# RPiHeatingArduinoOilSensor433.net
KiCad netlist of a schematic drawn in EAGLE
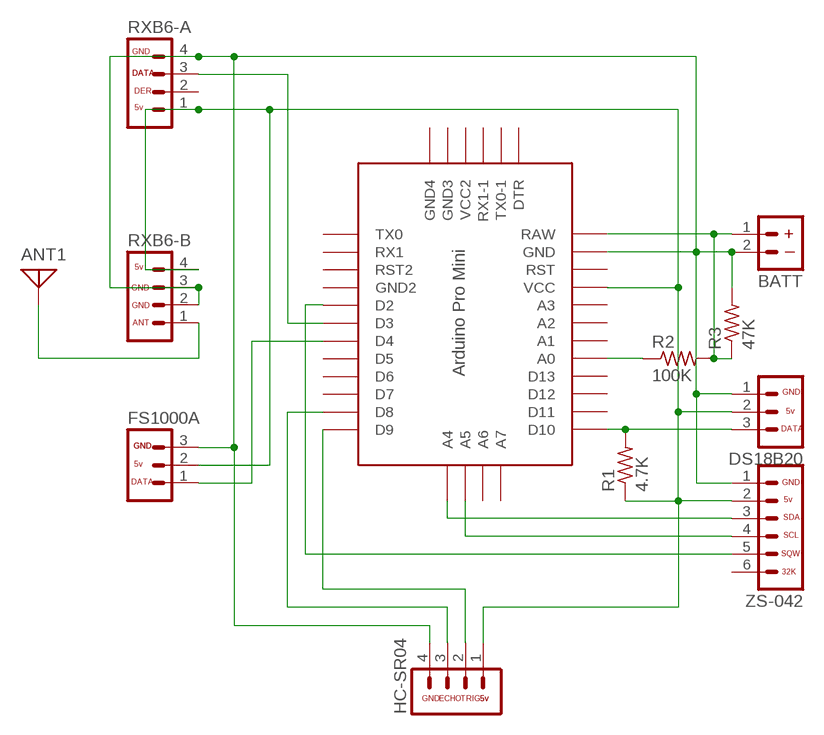
[diagram p0: schematic, sheet 1]

(export (version "E")
  (design (tool "Eeschema 10.0.6"))
  (components
    (comp (ref "ANT1")
      (value "ANTENNA")
      (footprint "eagle-import:PAD-01")
      (libsource (lib "eagle-import") (part "ANTENNA"))
    )
    (comp (ref "BATT")
      (value "M02PTH")
      (footprint "eagle-import:1X02")
      (libsource (lib "eagle-import") (part "M02PTH"))
    )
    (comp (ref "DS18B20")
      (value "M03JST-PTH-VERT")
      (footprint "eagle-import:JST-3-PTH-VERT")
      (libsource (lib "eagle-import") (part "M03JST-PTH-VERT"))
    )
    (comp (ref "FS1000A")
      (value "M03LONGPADS")
      (footprint "eagle-import:1X03_LONGPADS")
      (libsource (lib "eagle-import") (part "M03LONGPADS"))
    )
    (comp (ref "HC-SR04")
      (value "M04LONGPADS")
      (footprint "eagle-import:1X04_LONGPADS")
      (libsource (lib "eagle-import") (part "M04LONGPADS"))
    )
    (comp (ref "R1")
      (value "4.7K")
      (footprint "eagle-import:0204_7")
      (libsource (lib "eagle-import") (part "R-US_0204/7"))
    )
    (comp (ref "R2")
      (value "100K")
      (footprint "eagle-import:0207_10")
      (libsource (lib "eagle-import") (part "R-US_0207/10"))
    )
    (comp (ref "R3")
      (value "47K")
      (footprint "eagle-import:0207_10")
      (libsource (lib "eagle-import") (part "R-US_0207/10"))
    )
    (comp (ref "RXB6-A")
      (value "M04LONGPADS")
      (footprint "eagle-import:1X04_LONGPADS")
      (libsource (lib "eagle-import") (part "M04LONGPADS"))
    )
    (comp (ref "RXB6-B")
      (value "M04LONGPADS")
      (footprint "eagle-import:1X04_LONGPADS")
      (libsource (lib "eagle-import") (part "M04LONGPADS"))
    )
    (comp (ref "U$1")
      (value "PRO-MINI")
      (footprint "eagle-import:PRO-MINI")
      (libsource (lib "eagle-import") (part "PRO-MINI"))
    )
    (comp (ref "ZS-042")
      (value "M06LONGPADS")
      (footprint "eagle-import:1X06_LONGPADS")
      (libsource (lib "eagle-import") (part "M06LONGPADS"))
    )
  )
  (nets
    (net (code "1") (name "Net-(ANT1-Pad1)") (class "Default")
      (node (ref "ANT1") (pin "1") (pinfunction "1_1") (pintype "output"))
      (node (ref "RXB6-B") (pin "1") (pinfunction "1_1") (pintype "passive"))
    )
    (net (code "2") (name "Net-(BATT-Pad1)") (class "Default")
      (node (ref "BATT") (pin "1") (pinfunction "1_1") (pintype "passive"))
      (node (ref "R2") (pin "2") (pinfunction "2_2") (pintype "passive"))
      (node (ref "R3") (pin "1") (pinfunction "1_1") (pintype "passive"))
      (node (ref "U$1") (pin "RAW") (pinfunction "RAW_RAW") (pintype "power_in"))
    )
    (net (code "3") (name "Net-(BATT-Pad2)") (class "Default")
      (node (ref "BATT") (pin "2") (pinfunction "2_2") (pintype "passive"))
      (node (ref "DS18B20") (pin "1") (pinfunction "1_1") (pintype "passive"))
      (node (ref "FS1000A") (pin "3") (pinfunction "3_3") (pintype "passive"))
      (node (ref "HC-SR04") (pin "4") (pinfunction "4_4") (pintype "passive"))
      (node (ref "R3") (pin "2") (pinfunction "2_2") (pintype "passive"))
      (node (ref "RXB6-A") (pin "4") (pinfunction "4_4") (pintype "passive"))
      (node (ref "RXB6-B") (pin "2") (pinfunction "2_2") (pintype "passive"))
      (node (ref "RXB6-B") (pin "3") (pinfunction "3_3") (pintype "passive"))
      (node (ref "U$1") (pin "GND") (pinfunction "GND_GND") (pintype "input"))
      (node (ref "ZS-042") (pin "1") (pinfunction "1_1") (pintype "passive"))
    )
    (net (code "4") (name "Net-(DS18B20-Pad2)") (class "Default")
      (node (ref "DS18B20") (pin "2") (pinfunction "2_2") (pintype "passive"))
      (node (ref "FS1000A") (pin "2") (pinfunction "2_2") (pintype "passive"))
      (node (ref "HC-SR04") (pin "1") (pinfunction "1_1") (pintype "passive"))
      (node (ref "R1") (pin "1") (pinfunction "1_1") (pintype "passive"))
      (node (ref "RXB6-A") (pin "1") (pinfunction "1_1") (pintype "passive"))
      (node (ref "RXB6-B") (pin "4") (pinfunction "4_4") (pintype "passive"))
      (node (ref "U$1") (pin "VCC") (pinfunction "VCC_VCC") (pintype "bidirectional"))
      (node (ref "ZS-042") (pin "2") (pinfunction "2_2") (pintype "passive"))
    )
    (net (code "5") (name "Net-(DS18B20-Pad3)") (class "Default")
      (node (ref "DS18B20") (pin "3") (pinfunction "3_3") (pintype "passive"))
      (node (ref "R1") (pin "2") (pinfunction "2_2") (pintype "passive"))
      (node (ref "U$1") (pin "D10") (pinfunction "D10_D10") (pintype "bidirectional"))
    )
    (net (code "6") (name "Net-(FS1000A-Pad1)") (class "Default")
      (node (ref "FS1000A") (pin "1") (pinfunction "1_1") (pintype "passive"))
      (node (ref "U$1") (pin "D4") (pinfunction "D4_D4") (pintype "bidirectional"))
    )
    (net (code "7") (name "Net-(HC-SR04-Pad2)") (class "Default")
      (node (ref "HC-SR04") (pin "2") (pinfunction "2_2") (pintype "passive"))
      (node (ref "U$1") (pin "D9") (pinfunction "D9_D9") (pintype "bidirectional"))
    )
    (net (code "8") (name "Net-(HC-SR04-Pad3)") (class "Default")
      (node (ref "HC-SR04") (pin "3") (pinfunction "3_3") (pintype "passive"))
      (node (ref "U$1") (pin "D8") (pinfunction "D8_D8") (pintype "bidirectional"))
    )
    (net (code "9") (name "Net-(R2-Pad1)") (class "Default")
      (node (ref "R2") (pin "1") (pinfunction "1_1") (pintype "passive"))
      (node (ref "U$1") (pin "A0") (pinfunction "A0_A0") (pintype "bidirectional"))
    )
    (net (code "10") (name "Net-(RXB6-A-Pad3)") (class "Default")
      (node (ref "RXB6-A") (pin "3") (pinfunction "3_3") (pintype "passive"))
      (node (ref "U$1") (pin "D3") (pinfunction "D3_D3") (pintype "bidirectional"))
    )
    (net (code "11") (name "Net-(U$1-PadA4)") (class "Default")
      (node (ref "U$1") (pin "A4") (pinfunction "A4_A4") (pintype "bidirectional"))
      (node (ref "ZS-042") (pin "3") (pinfunction "3_3") (pintype "passive"))
    )
    (net (code "12") (name "Net-(U$1-PadA5)") (class "Default")
      (node (ref "U$1") (pin "A5") (pinfunction "A5_A5") (pintype "bidirectional"))
      (node (ref "ZS-042") (pin "4") (pinfunction "4_4") (pintype "passive"))
    )
    (net (code "13") (name "Net-(U$1-PadD2)") (class "Default")
      (node (ref "U$1") (pin "D2") (pinfunction "D2_D2") (pintype "bidirectional"))
      (node (ref "ZS-042") (pin "5") (pinfunction "5_5") (pintype "passive"))
    )
    (net (code "14") (name "unconnected-(RXB6-A-Pad2)") (class "Default")
      (node (ref "RXB6-A") (pin "2") (pinfunction "2_2") (pintype "passive"))
    )
    (net (code "15") (name "unconnected-(U$1-GND2-PadGND1)") (class "Default")
      (node (ref "U$1") (pin "GND1") (pinfunction "GND2_GND1") (pintype "bidirectional"))
    )
    (net (code "16") (name "unconnected-(U$1-GND4-PadGND2)") (class "Default")
      (node (ref "U$1") (pin "GND2") (pinfunction "GND4_GND2") (pintype "bidirectional"))
    )
    (net (code "17") (name "unconnected-(U$1-PadA1)") (class "Default")
      (node (ref "U$1") (pin "A1") (pinfunction "A1_A1") (pintype "bidirectional"))
    )
    (net (code "18") (name "unconnected-(U$1-PadA2)") (class "Default")
      (node (ref "U$1") (pin "A2") (pinfunction "A2_A2") (pintype "bidirectional"))
    )
    (net (code "19") (name "unconnected-(U$1-PadA3)") (class "Default")
      (node (ref "U$1") (pin "A3") (pinfunction "A3_A3") (pintype "bidirectional"))
    )
    (net (code "20") (name "unconnected-(U$1-PadA6)") (class "Default")
      (node (ref "U$1") (pin "A6") (pinfunction "A6_A6") (pintype "bidirectional"))
    )
    (net (code "21") (name "unconnected-(U$1-PadA7)") (class "Default")
      (node (ref "U$1") (pin "A7") (pinfunction "A7_A7") (pintype "bidirectional"))
    )
    (net (code "22") (name "unconnected-(U$1-PadD5)") (class "Default")
      (node (ref "U$1") (pin "D5") (pinfunction "D5_D5") (pintype "bidirectional"))
    )
    (net (code "23") (name "unconnected-(U$1-PadD6)") (class "Default")
      (node (ref "U$1") (pin "D6") (pinfunction "D6_D6") (pintype "bidirectional"))
    )
    (net (code "24") (name "unconnected-(U$1-PadD7)") (class "Default")
      (node (ref "U$1") (pin "D7") (pinfunction "D7_D7") (pintype "bidirectional"))
    )
    (net (code "25") (name "unconnected-(U$1-PadD11)") (class "Default")
      (node (ref "U$1") (pin "D11") (pinfunction "D11_D11") (pintype "bidirectional"))
    )
    (net (code "26") (name "unconnected-(U$1-PadD12)") (class "Default")
      (node (ref "U$1") (pin "D12") (pinfunction "D12_D12") (pintype "bidirectional"))
    )
    (net (code "27") (name "unconnected-(U$1-PadD13)") (class "Default")
      (node (ref "U$1") (pin "D13") (pinfunction "D13_D13") (pintype "bidirectional"))
    )
    (net (code "28") (name "unconnected-(U$1-PadDTR)") (class "Default")
      (node (ref "U$1") (pin "DTR") (pinfunction "DTR_DTR") (pintype "bidirectional"))
    )
    (net (code "29") (name "unconnected-(U$1-PadGND3)") (class "Default")
      (node (ref "U$1") (pin "GND3") (pinfunction "GND3_GND3") (pintype "bidirectional"))
    )
    (net (code "30") (name "unconnected-(U$1-PadRST)") (class "Default")
      (node (ref "U$1") (pin "RST") (pinfunction "RST_RST") (pintype "bidirectional"))
    )
    (net (code "31") (name "unconnected-(U$1-PadRX1)") (class "Default")
      (node (ref "U$1") (pin "RX1") (pinfunction "RX1_RX1") (pintype "bidirectional"))
    )
    (net (code "32") (name "unconnected-(U$1-PadRX1-1)") (class "Default")
      (node (ref "U$1") (pin "RX1-1") (pinfunction "RX1-1_RX1-1") (pintype "bidirectional"))
    )
    (net (code "33") (name "unconnected-(U$1-PadTX0)") (class "Default")
      (node (ref "U$1") (pin "TX0") (pinfunction "TX0_TX0") (pintype "bidirectional"))
    )
    (net (code "34") (name "unconnected-(U$1-PadTX0-1)") (class "Default")
      (node (ref "U$1") (pin "TX0-1") (pinfunction "TX0-1_TX0-1") (pintype "bidirectional"))
    )
    (net (code "35") (name "unconnected-(U$1-RST2-PadRST1)") (class "Default")
      (node (ref "U$1") (pin "RST1") (pinfunction "RST2_RST1") (pintype "bidirectional"))
    )
    (net (code "36") (name "unconnected-(U$1-VCC2-PadVCC1)") (class "Default")
      (node (ref "U$1") (pin "VCC1") (pinfunction "VCC2_VCC1") (pintype "bidirectional"))
    )
    (net (code "37") (name "unconnected-(ZS-042-Pad6)") (class "Default")
      (node (ref "ZS-042") (pin "6") (pinfunction "6_6") (pintype "passive"))
    )
  )
)
